# WCcircuit.net
KiCad netlist of a schematic drawn in Altium Designer
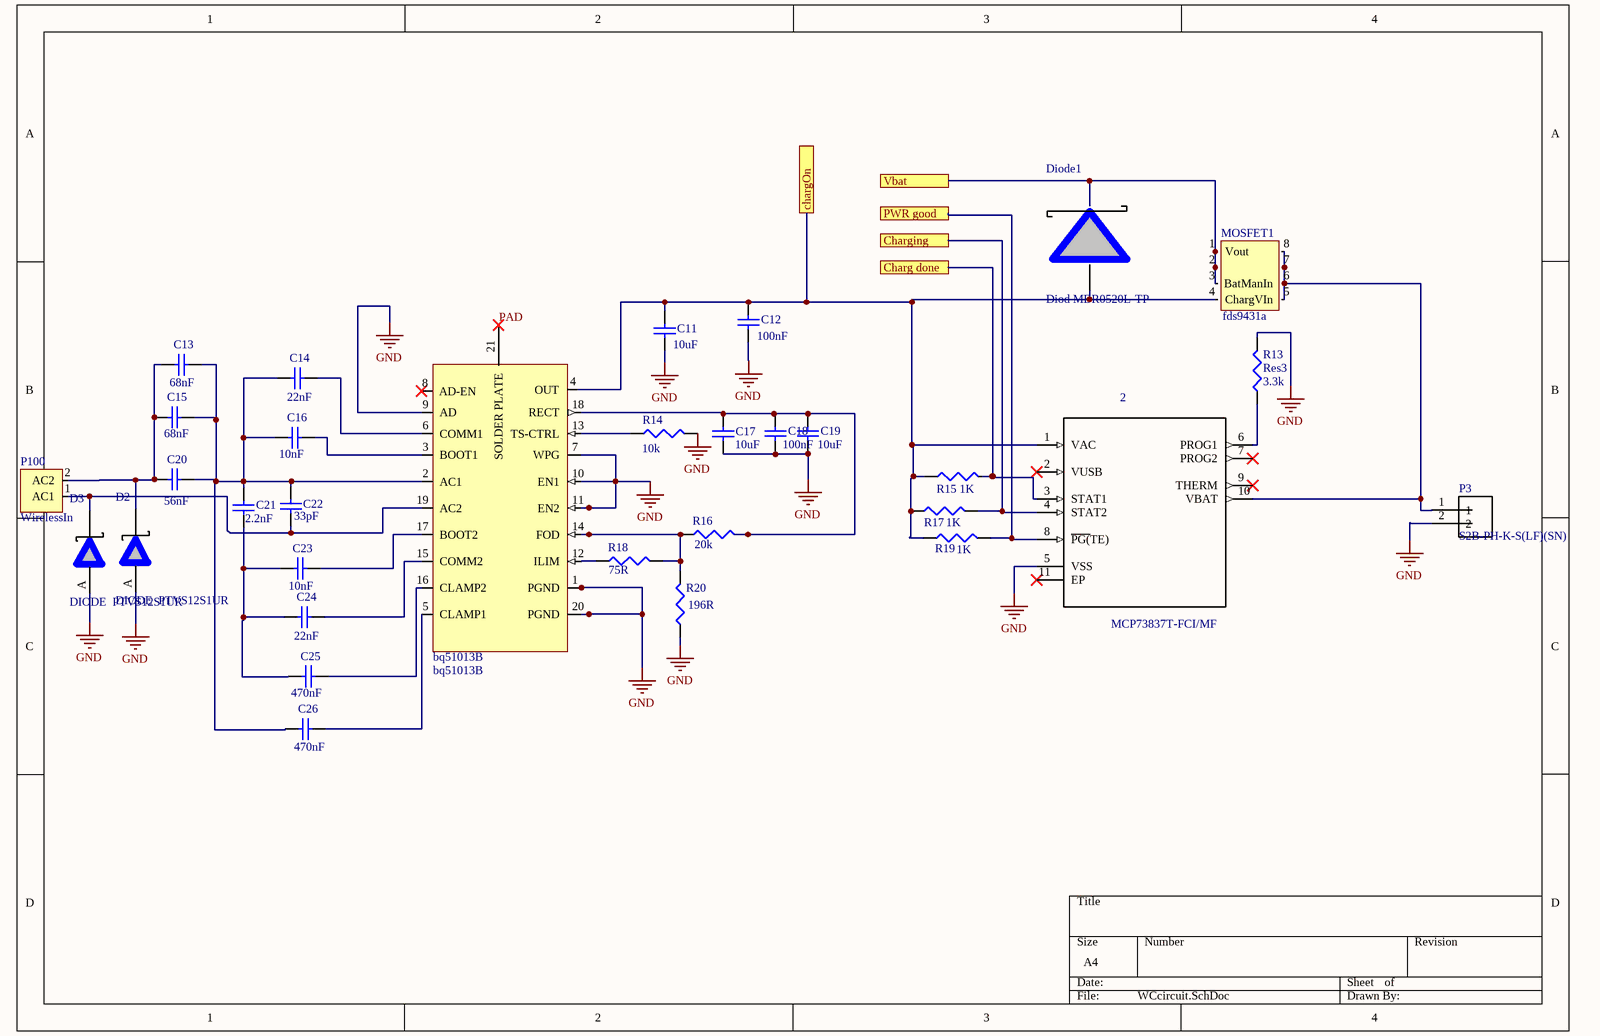
[diagram p0: WCcircuit.SchDoc]

(export (version "E")
  (design (tool "Eeschema 10.0.6"))
  (components
    (comp (ref "2")
      (value "MCP73837T-FCI/MF")
      (footprint "DFN300X300X100-11N")
      (description "MCP73837 Series 6 V Linear Battery Charge Controller Surface Mount - DFN-10")
      (fields (field (name "MF") "Microchip"))
      (libsource (lib "HGCDLibrary") (part "MCP73837T-FCI/MF"))
    )
    (comp (ref "bq51013B")
      (value "bq51013B")
      (footprint "CONTROLLER_MSP430FR2522IRHLT")
      (libsource (lib "HGCDLibrary") (part "bq51013B"))
    )
    (comp (ref "C11")
      (value "10uF")
      (footprint "1608[0603]")
      (description "Capacitor (Semiconductor SIM Model)")
      (fields (field (name "Comment") "Cap Semi") (field (name "PUBLISHER") "Altium Limited"))
      (libsource (lib "Miscellaneous Devices") (part "Cap Semi"))
    )
    (comp (ref "C12")
      (value "100nF")
      (footprint "1608[0603]")
      (description "Capacitor (Semiconductor SIM Model)")
      (fields (field (name "Comment") "Cap Semi") (field (name "PUBLISHER") "Altium Limited"))
      (libsource (lib "Miscellaneous Devices") (part "Cap Semi"))
    )
    (comp (ref "C13")
      (value "68nF")
      (footprint "1608[0603]")
      (description "Capacitor (Semiconductor SIM Model)")
      (fields (field (name "Comment") "Cap Semi") (field (name "PUBLISHER") "Altium Limited"))
      (libsource (lib "Miscellaneous Devices") (part "Cap Semi"))
    )
    (comp (ref "C14")
      (value "22nF")
      (footprint "1608[0603]")
      (description "Capacitor (Semiconductor SIM Model)")
      (fields (field (name "Comment") "Cap Semi") (field (name "PUBLISHER") "Altium Limited"))
      (libsource (lib "Miscellaneous Devices") (part "Cap Semi"))
    )
    (comp (ref "C15")
      (value "68nF")
      (footprint "1608[0603]")
      (description "Capacitor (Semiconductor SIM Model)")
      (fields (field (name "Comment") "Cap Semi") (field (name "PUBLISHER") "Altium Limited"))
      (libsource (lib "Miscellaneous Devices") (part "Cap Semi"))
    )
    (comp (ref "C16")
      (value "10nF")
      (footprint "1608[0603]")
      (description "Capacitor (Semiconductor SIM Model)")
      (fields (field (name "Comment") "Cap Semi") (field (name "PUBLISHER") "Altium Limited"))
      (libsource (lib "Miscellaneous Devices") (part "Cap Semi"))
    )
    (comp (ref "C17")
      (value "10uF")
      (footprint "1608[0603]")
      (description "Capacitor (Semiconductor SIM Model)")
      (fields (field (name "Comment") "Cap Semi") (field (name "PUBLISHER") "Altium Limited"))
      (libsource (lib "Miscellaneous Devices") (part "Cap Semi"))
    )
    (comp (ref "C18")
      (value "100nF")
      (footprint "1608[0603]")
      (description "Capacitor (Semiconductor SIM Model)")
      (fields (field (name "Comment") "Cap Semi") (field (name "PUBLISHER") "Altium Limited"))
      (libsource (lib "Miscellaneous Devices") (part "Cap Semi"))
    )
    (comp (ref "C19")
      (value "10uF")
      (footprint "1608[0603]")
      (description "Capacitor (Semiconductor SIM Model)")
      (fields (field (name "Comment") "Cap Semi") (field (name "PUBLISHER") "Altium Limited"))
      (libsource (lib "Miscellaneous Devices") (part "Cap Semi"))
    )
    (comp (ref "C20")
      (value "56nF")
      (footprint "1608[0603]")
      (description "Capacitor (Semiconductor SIM Model)")
      (fields (field (name "Comment") "Cap Semi") (field (name "PUBLISHER") "Altium Limited"))
      (libsource (lib "Miscellaneous Devices") (part "Cap Semi"))
    )
    (comp (ref "C21")
      (value "2.2nF")
      (footprint "1608[0603]")
      (description "Capacitor (Semiconductor SIM Model)")
      (fields (field (name "Comment") "Cap Semi") (field (name "PUBLISHER") "Altium Limited"))
      (libsource (lib "Miscellaneous Devices") (part "Cap Semi"))
    )
    (comp (ref "C22")
      (value "33pF")
      (footprint "1608[0603]")
      (description "Capacitor (Semiconductor SIM Model)")
      (fields (field (name "Comment") "Cap Semi") (field (name "PUBLISHER") "Altium Limited"))
      (libsource (lib "Miscellaneous Devices") (part "Cap Semi"))
    )
    (comp (ref "C23")
      (value "10nF")
      (footprint "1608[0603]")
      (description "Capacitor (Semiconductor SIM Model)")
      (fields (field (name "Comment") "Cap Semi") (field (name "PUBLISHER") "Altium Limited"))
      (libsource (lib "Miscellaneous Devices") (part "Cap Semi"))
    )
    (comp (ref "C24")
      (value "22nF")
      (footprint "1608[0603]")
      (description "Capacitor (Semiconductor SIM Model)")
      (fields (field (name "Comment") "Cap Semi") (field (name "PUBLISHER") "Altium Limited"))
      (libsource (lib "Miscellaneous Devices") (part "Cap Semi"))
    )
    (comp (ref "C25")
      (value "470nF")
      (footprint "1608[0603]")
      (description "Capacitor (Semiconductor SIM Model)")
      (fields (field (name "Comment") "Cap Semi") (field (name "PUBLISHER") "Altium Limited"))
      (libsource (lib "Miscellaneous Devices") (part "Cap Semi"))
    )
    (comp (ref "C26")
      (value "470nF")
      (footprint "1608[0603]")
      (description "Capacitor (Semiconductor SIM Model)")
      (fields (field (name "Comment") "Cap Semi") (field (name "PUBLISHER") "Altium Limited"))
      (libsource (lib "Miscellaneous Devices") (part "Cap Semi"))
    )
    (comp (ref "D2")
      (value "DIODE  PTVS12S1UR")
      (footprint "PTVS12S1UR")
      (libsource (lib "HGCDLibrary") (part "DIODE  PTVS12S1UR"))
    )
    (comp (ref "D3")
      (value "DIODE  PTVS12S1UR")
      (footprint "PTVS12S1UR")
      (libsource (lib "HGCDLibrary") (part "DIODE  PTVS12S1UR"))
    )
    (comp (ref "Diode1")
      (value "Diod MBR0520L-TP")
      (footprint "SOD3716X135N")
      (libsource (lib "HGCDLibrary") (part "Diod MBR0520L-TP"))
    )
    (comp (ref "MOSFET1")
      (value "fds9431a")
      (footprint "SOIC127P600X175-8N")
      (libsource (lib "HGCDLibrary") (part "fds9431a"))
    )
    (comp (ref "P3")
      (value "S2B-PH-K-S(LF)(SN)")
      (footprint "JST_S2B-PH-K-S(LF)(SN)")
      (description "Header Side Entry 2way")
      (fields (field (name "MP") "S2B-PH-K-S (LF)(SN)") (field (name "MF") "JST"))
      (libsource (lib "HGCDLibrary") (part "S2B-PH-K-S(LF)(SN)"))
    )
    (comp (ref "P100")
      (value "WirelessIn")
      (footprint "WirelessIn")
      (libsource (lib "HGCDLibrary") (part "WirelessIn"))
    )
    (comp (ref "R13")
      (value "Res3")
      (footprint "J1-0603")
      (description "Resistor")
      (fields (field (name "ALTIUM_VALUE") "3.3k") (field (name "PUBLISHER") "Altium Limited"))
      (libsource (lib "Miscellaneous Devices") (part "Res3"))
    )
    (comp (ref "R14")
      (value "10k")
      (footprint "J1-0603")
      (description "Resistor")
      (fields (field (name "Comment") "Res3") (field (name "PUBLISHER") "Altium Limited"))
      (libsource (lib "Miscellaneous Devices") (part "Res3"))
    )
    (comp (ref "R15")
      (value "1K")
      (footprint "J1-0603")
      (description "Resistor")
      (fields (field (name "Comment") "Res3") (field (name "PUBLISHER") "Altium Limited"))
      (libsource (lib "Miscellaneous Devices") (part "Res3"))
    )
    (comp (ref "R16")
      (value "20k")
      (footprint "J1-0603")
      (description "Resistor")
      (fields (field (name "Comment") "Res3") (field (name "PUBLISHER") "Altium Limited"))
      (libsource (lib "Miscellaneous Devices") (part "Res3"))
    )
    (comp (ref "R17")
      (value "1K")
      (footprint "J1-0603")
      (description "Resistor")
      (fields (field (name "Comment") "Res3") (field (name "PUBLISHER") "Altium Limited"))
      (libsource (lib "Miscellaneous Devices") (part "Res3"))
    )
    (comp (ref "R18")
      (value "75R")
      (footprint "J1-0603")
      (description "Resistor")
      (fields (field (name "Comment") "Res3") (field (name "PUBLISHER") "Altium Limited"))
      (libsource (lib "Miscellaneous Devices") (part "Res3"))
    )
    (comp (ref "R19")
      (value "1K")
      (footprint "J1-0603")
      (description "Resistor")
      (fields (field (name "Comment") "Res3") (field (name "PUBLISHER") "Altium Limited"))
      (libsource (lib "Miscellaneous Devices") (part "Res3"))
    )
    (comp (ref "R20")
      (value "196R")
      (footprint "J1-0603")
      (description "Resistor")
      (fields (field (name "Comment") "Res3") (field (name "PUBLISHER") "Altium Limited"))
      (libsource (lib "Miscellaneous Devices") (part "Res3"))
    )
  )
  (nets
    (net (code "1") (name "/Charg done") (class "Default")
      (node (ref "2") (pin "3") (pinfunction "STAT1_3") (pintype "input"))
      (node (ref "R15") (pin "2") (pinfunction "2_2") (pintype "passive"))
    )
    (net (code "2") (name "/Charging") (class "Default")
      (node (ref "2") (pin "4") (pinfunction "STAT2_4") (pintype "input"))
      (node (ref "R17") (pin "2") (pinfunction "2_2") (pintype "passive"))
    )
    (net (code "3") (name "/PAD") (class "Default")
      (node (ref "bq51013B") (pin "21") (pinfunction "SOLDER_PLATE_21") (pintype "open_collector+no_connect"))
    )
    (net (code "4") (name "/PWR good") (class "Default")
      (node (ref "2") (pin "8") (pinfunction "~{PG(}TE)_8") (pintype "input"))
      (node (ref "R19") (pin "2") (pinfunction "2_2") (pintype "passive"))
    )
    (net (code "5") (name "/Vbat") (class "Default")
      (node (ref "Diode1") (pin "C") (pinfunction "26_C") (pintype "passive"))
      (node (ref "MOSFET1") (pin "1") (pinfunction "Vout_1") (pintype "output"))
      (node (ref "MOSFET1") (pin "2") (pinfunction "22_2") (pintype "passive"))
      (node (ref "MOSFET1") (pin "3") (pinfunction "23_3") (pintype "passive"))
    )
    (net (code "6") (name "/chargOn") (class "Default")
      (node (ref "2") (pin "1") (pinfunction "VAC_1") (pintype "input"))
      (node (ref "C11") (pin "2") (pinfunction "2_2") (pintype "passive"))
      (node (ref "C12") (pin "2") (pinfunction "2_2") (pintype "passive"))
      (node (ref "Diode1") (pin "A") (pinfunction "26_A") (pintype "passive"))
      (node (ref "MOSFET1") (pin "4") (pinfunction "ChargVIn_4") (pintype "input"))
      (node (ref "R15") (pin "1") (pinfunction "1_1") (pintype "passive"))
      (node (ref "R17") (pin "1") (pinfunction "1_1") (pintype "passive"))
      (node (ref "R19") (pin "1") (pinfunction "1_1") (pintype "passive"))
      (node (ref "bq51013B") (pin "4") (pinfunction "OUT_4") (pintype "power_in"))
    )
    (net (code "7") (name "GND") (class "Default")
      (node (ref "2") (pin "5") (pinfunction "VSS_5") (pintype "power_in"))
      (node (ref "C11") (pin "1") (pinfunction "1_1") (pintype "passive"))
      (node (ref "C12") (pin "1") (pinfunction "1_1") (pintype "passive"))
      (node (ref "C17") (pin "1") (pinfunction "1_1") (pintype "passive"))
      (node (ref "C18") (pin "1") (pinfunction "1_1") (pintype "passive"))
      (node (ref "C19") (pin "1") (pinfunction "1_1") (pintype "passive"))
      (node (ref "D2") (pin "A") (pinfunction "26_A") (pintype "passive"))
      (node (ref "D3") (pin "A") (pinfunction "26_A") (pintype "passive"))
      (node (ref "P3") (pin "2") (pinfunction "2_2") (pintype "passive"))
      (node (ref "R13") (pin "2") (pinfunction "2_2") (pintype "passive"))
      (node (ref "R14") (pin "2") (pinfunction "2_2") (pintype "passive"))
      (node (ref "R20") (pin "1") (pinfunction "1_1") (pintype "passive"))
      (node (ref "bq51013B") (pin "1") (pinfunction "PGND_1") (pintype "power_in"))
      (node (ref "bq51013B") (pin "10") (pinfunction "EN1_10") (pintype "input"))
      (node (ref "bq51013B") (pin "11") (pinfunction "EN2_11") (pintype "input"))
      (node (ref "bq51013B") (pin "20") (pinfunction "PGND_20") (pintype "power_in"))
      (node (ref "bq51013B") (pin "7") (pinfunction "WPG_7") (pintype "power_in"))
      (node (ref "bq51013B") (pin "9") (pinfunction "AD_9") (pintype "power_in"))
    )
    (net (code "8") (name "Net-(2-PROG1)") (class "Default")
      (node (ref "2") (pin "6") (pinfunction "PROG1_6") (pintype "output"))
      (node (ref "R13") (pin "1") (pinfunction "1_1") (pintype "passive"))
    )
    (net (code "9") (name "Net-(2-VBAT)") (class "Default")
      (node (ref "2") (pin "10") (pinfunction "VBAT_10") (pintype "output"))
      (node (ref "MOSFET1") (pin "5") (pinfunction "22_5") (pintype "passive"))
      (node (ref "MOSFET1") (pin "6") (pinfunction "BatManIn_6") (pintype "input"))
      (node (ref "MOSFET1") (pin "7") (pinfunction "22_7") (pintype "passive"))
      (node (ref "MOSFET1") (pin "8") (pinfunction "22_8") (pintype "passive"))
      (node (ref "P3") (pin "1") (pinfunction "1_1") (pintype "passive"))
    )
    (net (code "10") (name "Net-(C21-Pad1)") (class "Default")
      (node (ref "C21") (pin "1") (pinfunction "1_1") (pintype "passive"))
      (node (ref "C23") (pin "1") (pinfunction "1_1") (pintype "passive"))
      (node (ref "C24") (pin "1") (pinfunction "1_1") (pintype "passive"))
      (node (ref "C25") (pin "1") (pinfunction "1_1") (pintype "passive"))
    )
    (net (code "11") (name "Net-(P100-AC1)") (class "Default")
      (node (ref "C22") (pin "1") (pinfunction "1_1") (pintype "passive"))
      (node (ref "D3") (pin "C") (pinfunction "26_C") (pintype "passive"))
      (node (ref "P100") (pin "1") (pinfunction "AC1_1") (pintype "passive"))
      (node (ref "bq51013B") (pin "19") (pinfunction "AC2_19") (pintype "input"))
    )
    (net (code "12") (name "Net-(P100-AC2)") (class "Default")
      (node (ref "C13") (pin "1") (pinfunction "1_1") (pintype "passive"))
      (node (ref "C15") (pin "1") (pinfunction "1_1") (pintype "passive"))
      (node (ref "C20") (pin "1") (pinfunction "1_1") (pintype "passive"))
      (node (ref "D2") (pin "C") (pinfunction "26_C") (pintype "passive"))
      (node (ref "P100") (pin "2") (pinfunction "AC2_2") (pintype "passive"))
    )
    (net (code "13") (name "Net-(bq51013B-AC1)") (class "Default")
      (node (ref "C13") (pin "2") (pinfunction "2_2") (pintype "passive"))
      (node (ref "C14") (pin "1") (pinfunction "1_1") (pintype "passive"))
      (node (ref "C15") (pin "2") (pinfunction "2_2") (pintype "passive"))
      (node (ref "C16") (pin "1") (pinfunction "1_1") (pintype "passive"))
      (node (ref "C20") (pin "2") (pinfunction "2_2") (pintype "passive"))
      (node (ref "C21") (pin "2") (pinfunction "2_2") (pintype "passive"))
      (node (ref "C22") (pin "2") (pinfunction "2_2") (pintype "passive"))
      (node (ref "C26") (pin "1") (pinfunction "1_1") (pintype "passive"))
      (node (ref "bq51013B") (pin "2") (pinfunction "AC1_2") (pintype "input"))
    )
    (net (code "14") (name "Net-(bq51013B-BOOT1)") (class "Default")
      (node (ref "C16") (pin "2") (pinfunction "2_2") (pintype "passive"))
      (node (ref "bq51013B") (pin "3") (pinfunction "BOOT1_3") (pintype "output"))
    )
    (net (code "15") (name "Net-(bq51013B-BOOT2)") (class "Default")
      (node (ref "C23") (pin "2") (pinfunction "2_2") (pintype "passive"))
      (node (ref "bq51013B") (pin "17") (pinfunction "BOOT2_17") (pintype "output"))
    )
    (net (code "16") (name "Net-(bq51013B-CLAMP1)") (class "Default")
      (node (ref "C26") (pin "2") (pinfunction "2_2") (pintype "passive"))
      (node (ref "bq51013B") (pin "5") (pinfunction "CLAMP1_5") (pintype "output"))
    )
    (net (code "17") (name "Net-(bq51013B-CLAMP2)") (class "Default")
      (node (ref "C25") (pin "2") (pinfunction "2_2") (pintype "passive"))
      (node (ref "bq51013B") (pin "16") (pinfunction "CLAMP2_16") (pintype "output"))
    )
    (net (code "18") (name "Net-(bq51013B-COMM1)") (class "Default")
      (node (ref "C14") (pin "2") (pinfunction "2_2") (pintype "passive"))
      (node (ref "bq51013B") (pin "6") (pinfunction "COMM1_6") (pintype "output"))
    )
    (net (code "19") (name "Net-(bq51013B-COMM2)") (class "Default")
      (node (ref "C24") (pin "2") (pinfunction "2_2") (pintype "passive"))
      (node (ref "bq51013B") (pin "15") (pinfunction "COMM2_15") (pintype "output"))
    )
    (net (code "20") (name "Net-(bq51013B-FOD)") (class "Default")
      (node (ref "R16") (pin "1") (pinfunction "1_1") (pintype "passive"))
      (node (ref "R18") (pin "2") (pinfunction "2_2") (pintype "passive"))
      (node (ref "R20") (pin "2") (pinfunction "2_2") (pintype "passive"))
      (node (ref "bq51013B") (pin "14") (pinfunction "FOD_14") (pintype "input"))
    )
    (net (code "21") (name "Net-(bq51013B-ILIM)") (class "Default")
      (node (ref "R18") (pin "1") (pinfunction "1_1") (pintype "passive"))
      (node (ref "bq51013B") (pin "12") (pinfunction "ILIM_12") (pintype "input"))
    )
    (net (code "22") (name "Net-(bq51013B-RECT)") (class "Default")
      (node (ref "C17") (pin "2") (pinfunction "2_2") (pintype "passive"))
      (node (ref "C18") (pin "2") (pinfunction "2_2") (pintype "passive"))
      (node (ref "C19") (pin "2") (pinfunction "2_2") (pintype "passive"))
      (node (ref "R16") (pin "2") (pinfunction "2_2") (pintype "passive"))
      (node (ref "bq51013B") (pin "18") (pinfunction "RECT_18") (pintype "output"))
    )
    (net (code "23") (name "Net-(bq51013B-TS-CTRL)") (class "Default")
      (node (ref "R14") (pin "1") (pinfunction "1_1") (pintype "passive"))
      (node (ref "bq51013B") (pin "13") (pinfunction "TS-CTRL_13") (pintype "input"))
    )
    (net (code "24") (name "unconnected-(2-EP-Pad11)") (class "Default")
      (node (ref "2") (pin "11") (pinfunction "EP_11") (pintype "passive+no_connect"))
    )
    (net (code "25") (name "unconnected-(2-PROG2-Pad7)") (class "Default")
      (node (ref "2") (pin "7") (pinfunction "PROG2_7") (pintype "output+no_connect"))
    )
    (net (code "26") (name "unconnected-(2-THERM-Pad9)") (class "Default")
      (node (ref "2") (pin "9") (pinfunction "THERM_9") (pintype "output+no_connect"))
    )
    (net (code "27") (name "unconnected-(2-VUSB-Pad2)") (class "Default")
      (node (ref "2") (pin "2") (pinfunction "VUSB_2") (pintype "input+no_connect"))
    )
    (net (code "28") (name "unconnected-(bq51013B-AD-EN-Pad8)") (class "Default")
      (node (ref "bq51013B") (pin "8") (pinfunction "AD-EN_8") (pintype "power_in+no_connect"))
    )
  )
)
